# Sheet2.net
KiCad netlist of a schematic drawn in Altium Designer
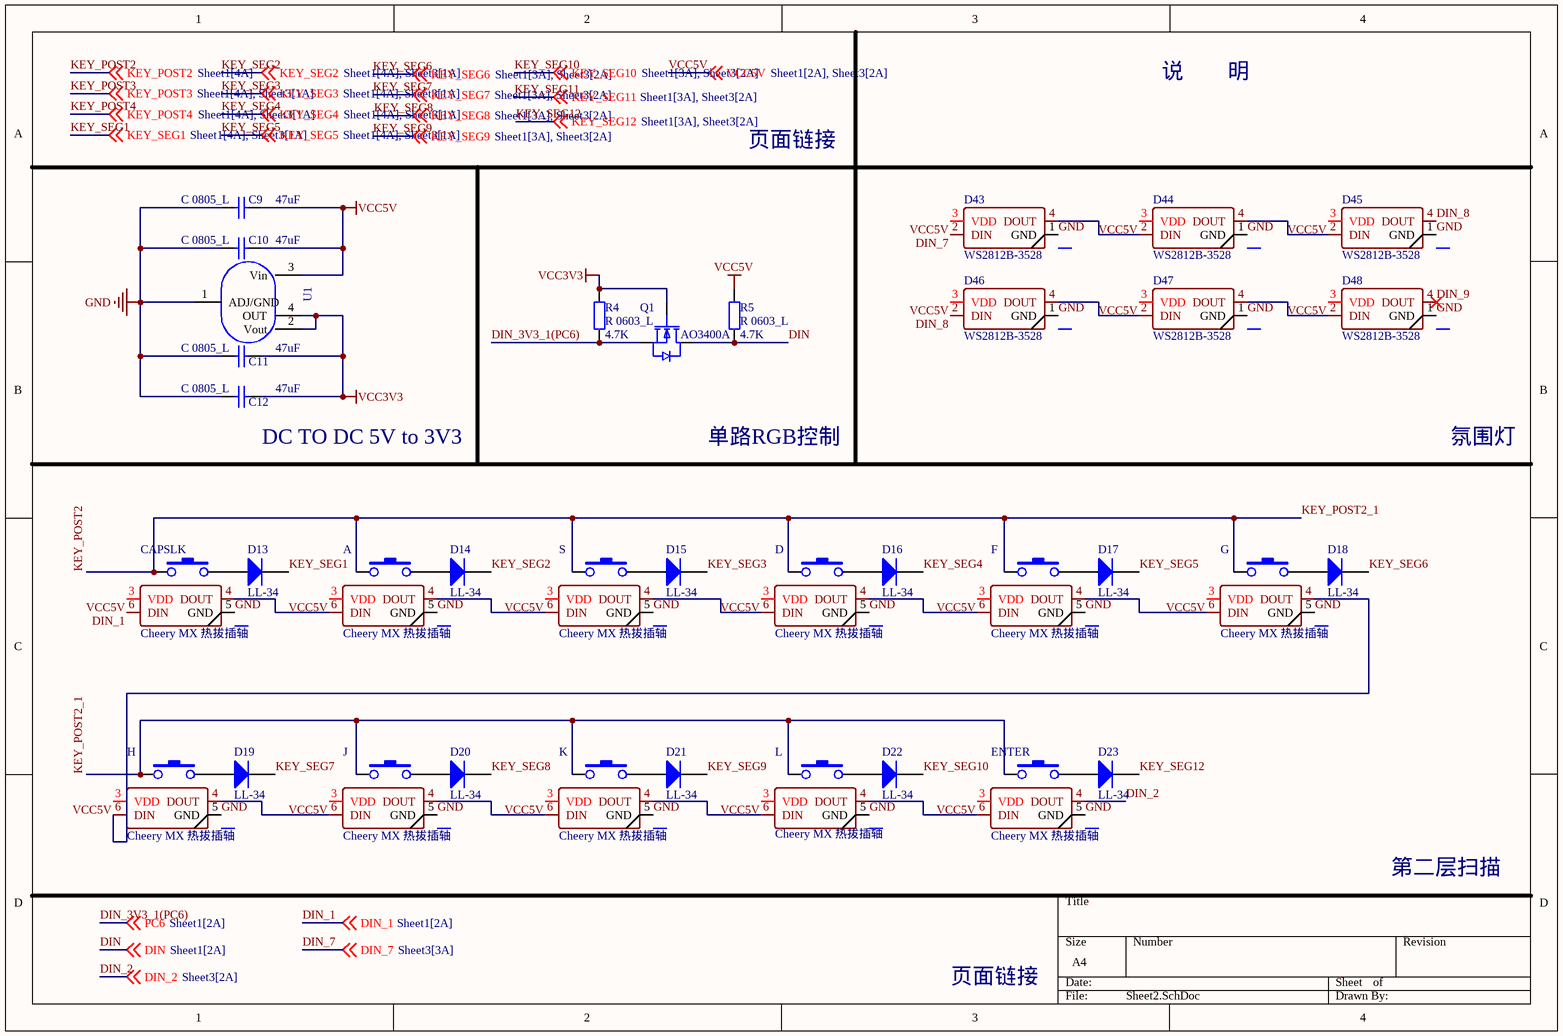
[diagram p0: Sheet2.SchDoc]

(export (version "E")
  (design (tool "Eeschema 10.0.6"))
  (components
    (comp (ref "A")
      (value "Cheery MX 热拔插轴")
      (footprint "MX_SW-HOTPLUG")
      (description "机械键盘轴（Cheery MX）")
      (libsource (lib "BaseLib") (part "Cheery MX 热拔插轴"))
    )
    (comp (ref "C9")
      (value "C 0805_L")
      (footprint "C 0805_L")
      (description "Capacitor")
      (fields (field (name "ALTIUM_VALUE") "47uF") (field (name "PUBLISHER") "Altium Limited"))
      (libsource (lib "Schlib1") (part "C 0805_L"))
    )
    (comp (ref "C10")
      (value "C 0805_L")
      (footprint "C 0805_L")
      (description "Capacitor")
      (fields (field (name "ALTIUM_VALUE") "47uF") (field (name "PUBLISHER") "Altium Limited"))
      (libsource (lib "Schlib1") (part "C 0805_L"))
    )
    (comp (ref "C11")
      (value "C 0805_L")
      (footprint "C 0805_L")
      (description "Capacitor")
      (fields (field (name "ALTIUM_VALUE") "47uF") (field (name "PUBLISHER") "Altium Limited"))
      (libsource (lib "Schlib1") (part "C 0805_L"))
    )
    (comp (ref "C12")
      (value "C 0805_L")
      (footprint "C 0805_L")
      (description "Capacitor")
      (fields (field (name "ALTIUM_VALUE") "47uF") (field (name "PUBLISHER") "Altium Limited"))
      (libsource (lib "Schlib1") (part "C 0805_L"))
    )
    (comp (ref "CAPSLK")
      (value "Cheery MX 热拔插轴")
      (footprint "MX_SW-HOTPLUG")
      (description "机械键盘轴（Cheery MX）")
      (libsource (lib "BaseLib") (part "Cheery MX 热拔插轴"))
    )
    (comp (ref "D")
      (value "Cheery MX 热拔插轴")
      (footprint "MX_SW-HOTPLUG")
      (description "机械键盘轴（Cheery MX）")
      (libsource (lib "BaseLib") (part "Cheery MX 热拔插轴"))
    )
    (comp (ref "D13")
      (value "LL-34")
      (footprint "LL-34_L3.7-W1.6-RD")
      (description "开关二极管（Switching diode）")
      (fields (field (name "PUBLISHER") "Altium Limited"))
      (libsource (lib "BaseLib") (part "LL4148"))
    )
    (comp (ref "D14")
      (value "LL-34")
      (footprint "LL-34_L3.7-W1.6-RD")
      (description "开关二极管（Switching diode）")
      (fields (field (name "PUBLISHER") "Altium Limited"))
      (libsource (lib "BaseLib") (part "LL4148"))
    )
    (comp (ref "D15")
      (value "LL-34")
      (footprint "LL-34_L3.7-W1.6-RD")
      (description "开关二极管（Switching diode）")
      (fields (field (name "PUBLISHER") "Altium Limited"))
      (libsource (lib "BaseLib") (part "LL4148"))
    )
    (comp (ref "D16")
      (value "LL-34")
      (footprint "LL-34_L3.7-W1.6-RD")
      (description "开关二极管（Switching diode）")
      (fields (field (name "PUBLISHER") "Altium Limited"))
      (libsource (lib "BaseLib") (part "LL4148"))
    )
    (comp (ref "D17")
      (value "LL-34")
      (footprint "LL-34_L3.7-W1.6-RD")
      (description "开关二极管（Switching diode）")
      (fields (field (name "PUBLISHER") "Altium Limited"))
      (libsource (lib "BaseLib") (part "LL4148"))
    )
    (comp (ref "D18")
      (value "LL-34")
      (footprint "LL-34_L3.7-W1.6-RD")
      (description "开关二极管（Switching diode）")
      (fields (field (name "PUBLISHER") "Altium Limited"))
      (libsource (lib "BaseLib") (part "LL4148"))
    )
    (comp (ref "D19")
      (value "LL-34")
      (footprint "LL-34_L3.7-W1.6-RD")
      (description "开关二极管（Switching diode）")
      (fields (field (name "PUBLISHER") "Altium Limited"))
      (libsource (lib "BaseLib") (part "LL4148"))
    )
    (comp (ref "D20")
      (value "LL-34")
      (footprint "LL-34_L3.7-W1.6-RD")
      (description "开关二极管（Switching diode）")
      (fields (field (name "PUBLISHER") "Altium Limited"))
      (libsource (lib "BaseLib") (part "LL4148"))
    )
    (comp (ref "D21")
      (value "LL-34")
      (footprint "LL-34_L3.7-W1.6-RD")
      (description "开关二极管（Switching diode）")
      (fields (field (name "PUBLISHER") "Altium Limited"))
      (libsource (lib "BaseLib") (part "LL4148"))
    )
    (comp (ref "D22")
      (value "LL-34")
      (footprint "LL-34_L3.7-W1.6-RD")
      (description "开关二极管（Switching diode）")
      (fields (field (name "PUBLISHER") "Altium Limited"))
      (libsource (lib "BaseLib") (part "LL4148"))
    )
    (comp (ref "D23")
      (value "LL-34")
      (footprint "LL-34_L3.7-W1.6-RD")
      (description "开关二极管（Switching diode）")
      (fields (field (name "PUBLISHER") "Altium Limited"))
      (libsource (lib "BaseLib") (part "LL4148"))
    )
    (comp (ref "D43")
      (value "WS2812B-3528")
      (footprint "WS2812B-3528，反贴RGBLED灯")
      (description "WS2812B-3528,反贴LED，RGB灯")
      (libsource (lib "BaseLib") (part "WS2812B-3528"))
    )
    (comp (ref "D44")
      (value "WS2812B-3528")
      (footprint "WS2812B-3528，反贴RGBLED灯")
      (description "WS2812B-3528,反贴LED，RGB灯")
      (libsource (lib "BaseLib") (part "WS2812B-3528"))
    )
    (comp (ref "D45")
      (value "WS2812B-3528")
      (footprint "WS2812B-3528，反贴RGBLED灯")
      (description "WS2812B-3528,反贴LED，RGB灯")
      (libsource (lib "BaseLib") (part "WS2812B-3528"))
    )
    (comp (ref "D46")
      (value "WS2812B-3528")
      (footprint "WS2812B-3528，反贴RGBLED灯")
      (description "WS2812B-3528,反贴LED，RGB灯")
      (libsource (lib "BaseLib") (part "WS2812B-3528"))
    )
    (comp (ref "D47")
      (value "WS2812B-3528")
      (footprint "WS2812B-3528，反贴RGBLED灯")
      (description "WS2812B-3528,反贴LED，RGB灯")
      (libsource (lib "BaseLib") (part "WS2812B-3528"))
    )
    (comp (ref "D48")
      (value "WS2812B-3528")
      (footprint "WS2812B-3528，反贴RGBLED灯")
      (description "WS2812B-3528,反贴LED，RGB灯")
      (libsource (lib "BaseLib") (part "WS2812B-3528"))
    )
    (comp (ref "ENTER")
      (value "Cheery MX 热拔插轴")
      (footprint "MX_SW-HOTPLUG")
      (description "机械键盘轴（Cheery MX）")
      (libsource (lib "BaseLib") (part "Cheery MX 热拔插轴"))
    )
    (comp (ref "F")
      (value "Cheery MX 热拔插轴")
      (footprint "MX_SW-HOTPLUG")
      (description "机械键盘轴（Cheery MX）")
      (libsource (lib "BaseLib") (part "Cheery MX 热拔插轴"))
    )
    (comp (ref "G")
      (value "Cheery MX 热拔插轴")
      (footprint "MX_SW-HOTPLUG")
      (description "机械键盘轴（Cheery MX）")
      (libsource (lib "BaseLib") (part "Cheery MX 热拔插轴"))
    )
    (comp (ref "H")
      (value "Cheery MX 热拔插轴")
      (footprint "MX_SW-HOTPLUG")
      (description "机械键盘轴（Cheery MX）")
      (libsource (lib "BaseLib") (part "Cheery MX 热拔插轴"))
    )
    (comp (ref "J")
      (value "Cheery MX 热拔插轴")
      (footprint "MX_SW-HOTPLUG")
      (description "机械键盘轴（Cheery MX）")
      (libsource (lib "BaseLib") (part "Cheery MX 热拔插轴"))
    )
    (comp (ref "K")
      (value "Cheery MX 热拔插轴")
      (footprint "MX_SW-HOTPLUG")
      (description "机械键盘轴（Cheery MX）")
      (libsource (lib "BaseLib") (part "Cheery MX 热拔插轴"))
    )
    (comp (ref "L")
      (value "Cheery MX 热拔插轴")
      (footprint "MX_SW-HOTPLUG")
      (description "机械键盘轴（Cheery MX）")
      (libsource (lib "BaseLib") (part "Cheery MX 热拔插轴"))
    )
    (comp (ref "Q1")
      (value "AO3400A")
      (footprint "AO3400A")
      (fields (field (name "MANUFACTURER") "Nexperia(安世)") (field (name "MANUFACTURER PART") "2N7002,215"))
      (libsource (lib "Schlib1") (part "2N7002,215"))
    )
    (comp (ref "R4")
      (value "R 0603_L")
      (footprint "R 0603_L")
      (description "Resistor")
      (fields (field (name "ALTIUM_VALUE") "4.7K") (field (name "PUBLISHER") "Altium Limited"))
      (libsource (lib "Schlib1") (part "R 0603_L"))
    )
    (comp (ref "R5")
      (value "R 0603_L")
      (footprint "R 0603_L")
      (description "Resistor")
      (fields (field (name "ALTIUM_VALUE") "4.7K") (field (name "PUBLISHER") "Altium Limited"))
      (libsource (lib "Schlib1") (part "R 0603_L"))
    )
    (comp (ref "S")
      (value "Cheery MX 热拔插轴")
      (footprint "MX_SW-HOTPLUG")
      (description "机械键盘轴（Cheery MX）")
      (libsource (lib "BaseLib") (part "Cheery MX 热拔插轴"))
    )
    (comp (ref "U1")
      (value "SPX1117M3-L-3-3")
      (footprint "SPX1117M3-L-3-3/TR")
      (fields (field (name "MANUFACTURER") "UTC(友顺)") (field (name "MANUFACTURER PART") "LM317G-AA3-R"))
      (libsource (lib "Schlib1") (part "SPX1117M3-L-3-3"))
    )
  )
  (nets
    (net (code "1") (name "/DIN_8") (class "Default")
      (node (ref "D45") (pin "4") (pinfunction "DOUT_4") (pintype "passive"))
      (node (ref "D46") (pin "2") (pinfunction "DIN_2") (pintype "passive"))
    )
    (net (code "2") (name "/DIN_9") (class "Default")
      (node (ref "D48") (pin "4") (pinfunction "DOUT_4") (pintype "passive+no_connect"))
    )
    (net (code "3") (name "DIN") (class "Default")
      (node (ref "Q1") (pin "3") (pinfunction "D_3") (pintype "passive"))
      (node (ref "R5") (pin "1") (pinfunction "1_1") (pintype "passive"))
    )
    (net (code "4") (name "DIN_1") (class "Default")
      (node (ref "CAPSLK") (pin "6") (pinfunction "DIN_6") (pintype "passive"))
    )
    (net (code "5") (name "DIN_2") (class "Default")
      (node (ref "ENTER") (pin "4") (pinfunction "DOUT_4") (pintype "passive"))
    )
    (net (code "6") (name "DIN_7") (class "Default")
      (node (ref "D43") (pin "2") (pinfunction "DIN_2") (pintype "passive"))
    )
    (net (code "7") (name "GND") (class "Default")
      (node (ref "A") (pin "5") (pinfunction "GND_5") (pintype "passive"))
      (node (ref "C10") (pin "1") (pinfunction "1_1") (pintype "passive"))
      (node (ref "C11") (pin "1") (pinfunction "1_1") (pintype "passive"))
      (node (ref "C12") (pin "1") (pinfunction "1_1") (pintype "passive"))
      (node (ref "C9") (pin "1") (pinfunction "1_1") (pintype "passive"))
      (node (ref "CAPSLK") (pin "5") (pinfunction "GND_5") (pintype "passive"))
      (node (ref "D") (pin "5") (pinfunction "GND_5") (pintype "passive"))
      (node (ref "D43") (pin "1") (pinfunction "GND_1") (pintype "passive"))
      (node (ref "D44") (pin "1") (pinfunction "GND_1") (pintype "passive"))
      (node (ref "D45") (pin "1") (pinfunction "GND_1") (pintype "passive"))
      (node (ref "D46") (pin "1") (pinfunction "GND_1") (pintype "passive"))
      (node (ref "D47") (pin "1") (pinfunction "GND_1") (pintype "passive"))
      (node (ref "D48") (pin "1") (pinfunction "GND_1") (pintype "passive"))
      (node (ref "ENTER") (pin "5") (pinfunction "GND_5") (pintype "passive"))
      (node (ref "F") (pin "5") (pinfunction "GND_5") (pintype "passive"))
      (node (ref "G") (pin "5") (pinfunction "GND_5") (pintype "passive"))
      (node (ref "H") (pin "5") (pinfunction "GND_5") (pintype "passive"))
      (node (ref "J") (pin "5") (pinfunction "GND_5") (pintype "passive"))
      (node (ref "K") (pin "5") (pinfunction "GND_5") (pintype "passive"))
      (node (ref "L") (pin "5") (pinfunction "GND_5") (pintype "passive"))
      (node (ref "S") (pin "5") (pinfunction "GND_5") (pintype "passive"))
      (node (ref "U1") (pin "1") (pinfunction "ADJ/GND_1") (pintype "passive"))
    )
    (net (code "8") (name "KEY_POST2") (class "Default")
      (node (ref "A") (pin "1") (pinfunction "1_1") (pintype "passive"))
      (node (ref "CAPSLK") (pin "1") (pinfunction "1_1") (pintype "passive"))
      (node (ref "D") (pin "1") (pinfunction "1_1") (pintype "passive"))
      (node (ref "ENTER") (pin "1") (pinfunction "1_1") (pintype "passive"))
      (node (ref "F") (pin "1") (pinfunction "1_1") (pintype "passive"))
      (node (ref "G") (pin "1") (pinfunction "1_1") (pintype "passive"))
      (node (ref "H") (pin "1") (pinfunction "1_1") (pintype "passive"))
      (node (ref "J") (pin "1") (pinfunction "1_1") (pintype "passive"))
      (node (ref "K") (pin "1") (pinfunction "1_1") (pintype "passive"))
      (node (ref "L") (pin "1") (pinfunction "1_1") (pintype "passive"))
      (node (ref "S") (pin "1") (pinfunction "1_1") (pintype "passive"))
    )
    (net (code "11") (name "KEY_SEG1") (class "Default")
      (node (ref "D13") (pin "2") (pinfunction "K_2") (pintype "passive"))
    )
    (net (code "12") (name "KEY_SEG2") (class "Default")
      (node (ref "D14") (pin "2") (pinfunction "K_2") (pintype "passive"))
    )
    (net (code "13") (name "KEY_SEG3") (class "Default")
      (node (ref "D15") (pin "2") (pinfunction "K_2") (pintype "passive"))
    )
    (net (code "14") (name "KEY_SEG4") (class "Default")
      (node (ref "D16") (pin "2") (pinfunction "K_2") (pintype "passive"))
    )
    (net (code "15") (name "KEY_SEG5") (class "Default")
      (node (ref "D17") (pin "2") (pinfunction "K_2") (pintype "passive"))
    )
    (net (code "16") (name "KEY_SEG6") (class "Default")
      (node (ref "D18") (pin "2") (pinfunction "K_2") (pintype "passive"))
    )
    (net (code "17") (name "KEY_SEG7") (class "Default")
      (node (ref "D19") (pin "2") (pinfunction "K_2") (pintype "passive"))
    )
    (net (code "18") (name "KEY_SEG8") (class "Default")
      (node (ref "D20") (pin "2") (pinfunction "K_2") (pintype "passive"))
    )
    (net (code "19") (name "KEY_SEG9") (class "Default")
      (node (ref "D21") (pin "2") (pinfunction "K_2") (pintype "passive"))
    )
    (net (code "20") (name "KEY_SEG10") (class "Default")
      (node (ref "D22") (pin "2") (pinfunction "K_2") (pintype "passive"))
    )
    (net (code "22") (name "KEY_SEG12") (class "Default")
      (node (ref "D23") (pin "2") (pinfunction "K_2") (pintype "passive"))
    )
    (net (code "23") (name "Net-(A-DIN)") (class "Default")
      (node (ref "A") (pin "6") (pinfunction "DIN_6") (pintype "passive"))
      (node (ref "CAPSLK") (pin "4") (pinfunction "DOUT_4") (pintype "passive"))
    )
    (net (code "24") (name "Net-(A-DOUT)") (class "Default")
      (node (ref "A") (pin "4") (pinfunction "DOUT_4") (pintype "passive"))
      (node (ref "S") (pin "6") (pinfunction "DIN_6") (pintype "passive"))
    )
    (net (code "25") (name "Net-(D-DIN)") (class "Default")
      (node (ref "D") (pin "6") (pinfunction "DIN_6") (pintype "passive"))
      (node (ref "S") (pin "4") (pinfunction "DOUT_4") (pintype "passive"))
    )
    (net (code "26") (name "Net-(D-DOUT)") (class "Default")
      (node (ref "D") (pin "4") (pinfunction "DOUT_4") (pintype "passive"))
      (node (ref "F") (pin "6") (pinfunction "DIN_6") (pintype "passive"))
    )
    (net (code "27") (name "Net-(D13-A)") (class "Default")
      (node (ref "CAPSLK") (pin "2") (pinfunction "2_2") (pintype "passive"))
      (node (ref "D13") (pin "1") (pinfunction "A_1") (pintype "passive"))
    )
    (net (code "28") (name "Net-(D14-A)") (class "Default")
      (node (ref "A") (pin "2") (pinfunction "2_2") (pintype "passive"))
      (node (ref "D14") (pin "1") (pinfunction "A_1") (pintype "passive"))
    )
    (net (code "29") (name "Net-(D15-A)") (class "Default")
      (node (ref "D15") (pin "1") (pinfunction "A_1") (pintype "passive"))
      (node (ref "S") (pin "2") (pinfunction "2_2") (pintype "passive"))
    )
    (net (code "30") (name "Net-(D16-A)") (class "Default")
      (node (ref "D") (pin "2") (pinfunction "2_2") (pintype "passive"))
      (node (ref "D16") (pin "1") (pinfunction "A_1") (pintype "passive"))
    )
    (net (code "31") (name "Net-(D17-A)") (class "Default")
      (node (ref "D17") (pin "1") (pinfunction "A_1") (pintype "passive"))
      (node (ref "F") (pin "2") (pinfunction "2_2") (pintype "passive"))
    )
    (net (code "32") (name "Net-(D18-A)") (class "Default")
      (node (ref "D18") (pin "1") (pinfunction "A_1") (pintype "passive"))
      (node (ref "G") (pin "2") (pinfunction "2_2") (pintype "passive"))
    )
    (net (code "33") (name "Net-(D19-A)") (class "Default")
      (node (ref "D19") (pin "1") (pinfunction "A_1") (pintype "passive"))
      (node (ref "H") (pin "2") (pinfunction "2_2") (pintype "passive"))
    )
    (net (code "34") (name "Net-(D20-A)") (class "Default")
      (node (ref "D20") (pin "1") (pinfunction "A_1") (pintype "passive"))
      (node (ref "J") (pin "2") (pinfunction "2_2") (pintype "passive"))
    )
    (net (code "35") (name "Net-(D21-A)") (class "Default")
      (node (ref "D21") (pin "1") (pinfunction "A_1") (pintype "passive"))
      (node (ref "K") (pin "2") (pinfunction "2_2") (pintype "passive"))
    )
    (net (code "36") (name "Net-(D22-A)") (class "Default")
      (node (ref "D22") (pin "1") (pinfunction "A_1") (pintype "passive"))
      (node (ref "L") (pin "2") (pinfunction "2_2") (pintype "passive"))
    )
    (net (code "37") (name "Net-(D23-A)") (class "Default")
      (node (ref "D23") (pin "1") (pinfunction "A_1") (pintype "passive"))
      (node (ref "ENTER") (pin "2") (pinfunction "2_2") (pintype "passive"))
    )
    (net (code "38") (name "Net-(D43-DOUT)") (class "Default")
      (node (ref "D43") (pin "4") (pinfunction "DOUT_4") (pintype "passive"))
      (node (ref "D44") (pin "2") (pinfunction "DIN_2") (pintype "passive"))
    )
    (net (code "39") (name "Net-(D44-DOUT)") (class "Default")
      (node (ref "D44") (pin "4") (pinfunction "DOUT_4") (pintype "passive"))
      (node (ref "D45") (pin "2") (pinfunction "DIN_2") (pintype "passive"))
    )
    (net (code "40") (name "Net-(D46-DOUT)") (class "Default")
      (node (ref "D46") (pin "4") (pinfunction "DOUT_4") (pintype "passive"))
      (node (ref "D47") (pin "2") (pinfunction "DIN_2") (pintype "passive"))
    )
    (net (code "41") (name "Net-(D47-DOUT)") (class "Default")
      (node (ref "D47") (pin "4") (pinfunction "DOUT_4") (pintype "passive"))
      (node (ref "D48") (pin "2") (pinfunction "DIN_2") (pintype "passive"))
    )
    (net (code "42") (name "Net-(ENTER-DIN)") (class "Default")
      (node (ref "ENTER") (pin "6") (pinfunction "DIN_6") (pintype "passive"))
      (node (ref "L") (pin "4") (pinfunction "DOUT_4") (pintype "passive"))
    )
    (net (code "43") (name "Net-(F-DOUT)") (class "Default")
      (node (ref "F") (pin "4") (pinfunction "DOUT_4") (pintype "passive"))
      (node (ref "G") (pin "6") (pinfunction "DIN_6") (pintype "passive"))
    )
    (net (code "44") (name "Net-(G-DOUT)") (class "Default")
      (node (ref "G") (pin "4") (pinfunction "DOUT_4") (pintype "passive"))
      (node (ref "H") (pin "6") (pinfunction "DIN_6") (pintype "passive"))
    )
    (net (code "45") (name "Net-(H-DOUT)") (class "Default")
      (node (ref "H") (pin "4") (pinfunction "DOUT_4") (pintype "passive"))
      (node (ref "J") (pin "6") (pinfunction "DIN_6") (pintype "passive"))
    )
    (net (code "46") (name "Net-(J-DOUT)") (class "Default")
      (node (ref "J") (pin "4") (pinfunction "DOUT_4") (pintype "passive"))
      (node (ref "K") (pin "6") (pinfunction "DIN_6") (pintype "passive"))
    )
    (net (code "47") (name "Net-(K-DOUT)") (class "Default")
      (node (ref "K") (pin "4") (pinfunction "DOUT_4") (pintype "passive"))
      (node (ref "L") (pin "6") (pinfunction "DIN_6") (pintype "passive"))
    )
    (net (code "48") (name "PC6") (class "Default")
      (node (ref "Q1") (pin "2") (pinfunction "S_2") (pintype "passive"))
      (node (ref "R4") (pin "1") (pinfunction "1_1") (pintype "passive"))
    )
    (net (code "49") (name "VCC3V3") (class "Default")
      (node (ref "C11") (pin "2") (pinfunction "2_2") (pintype "passive"))
      (node (ref "C12") (pin "2") (pinfunction "2_2") (pintype "passive"))
      (node (ref "Q1") (pin "1") (pinfunction "G_1") (pintype "passive"))
      (node (ref "R4") (pin "2") (pinfunction "2_2") (pintype "passive"))
      (node (ref "U1") (pin "2") (pinfunction "Vout_2") (pintype "passive"))
      (node (ref "U1") (pin "4") (pinfunction "OUT_4") (pintype "passive"))
    )
    (net (code "50") (name "VCC5V") (class "Default")
      (node (ref "A") (pin "3") (pinfunction "VDD_3") (pintype "passive"))
      (node (ref "C10") (pin "2") (pinfunction "2_2") (pintype "passive"))
      (node (ref "C9") (pin "2") (pinfunction "2_2") (pintype "passive"))
      (node (ref "CAPSLK") (pin "3") (pinfunction "VDD_3") (pintype "passive"))
      (node (ref "D") (pin "3") (pinfunction "VDD_3") (pintype "passive"))
      (node (ref "D43") (pin "3") (pinfunction "VDD_3") (pintype "passive"))
      (node (ref "D44") (pin "3") (pinfunction "VDD_3") (pintype "passive"))
      (node (ref "D45") (pin "3") (pinfunction "VDD_3") (pintype "passive"))
      (node (ref "D46") (pin "3") (pinfunction "VDD_3") (pintype "passive"))
      (node (ref "D47") (pin "3") (pinfunction "VDD_3") (pintype "passive"))
      (node (ref "D48") (pin "3") (pinfunction "VDD_3") (pintype "passive"))
      (node (ref "ENTER") (pin "3") (pinfunction "VDD_3") (pintype "passive"))
      (node (ref "F") (pin "3") (pinfunction "VDD_3") (pintype "passive"))
      (node (ref "G") (pin "3") (pinfunction "VDD_3") (pintype "passive"))
      (node (ref "H") (pin "3") (pinfunction "VDD_3") (pintype "passive"))
      (node (ref "J") (pin "3") (pinfunction "VDD_3") (pintype "passive"))
      (node (ref "K") (pin "3") (pinfunction "VDD_3") (pintype "passive"))
      (node (ref "L") (pin "3") (pinfunction "VDD_3") (pintype "passive"))
      (node (ref "R5") (pin "2") (pinfunction "2_2") (pintype "passive"))
      (node (ref "S") (pin "3") (pinfunction "VDD_3") (pintype "passive"))
      (node (ref "U1") (pin "3") (pinfunction "Vin_3") (pintype "passive"))
    )
  )
)
